# STM32_Home_Automation.net
KiCad netlist of a schematic drawn in Altium Designer
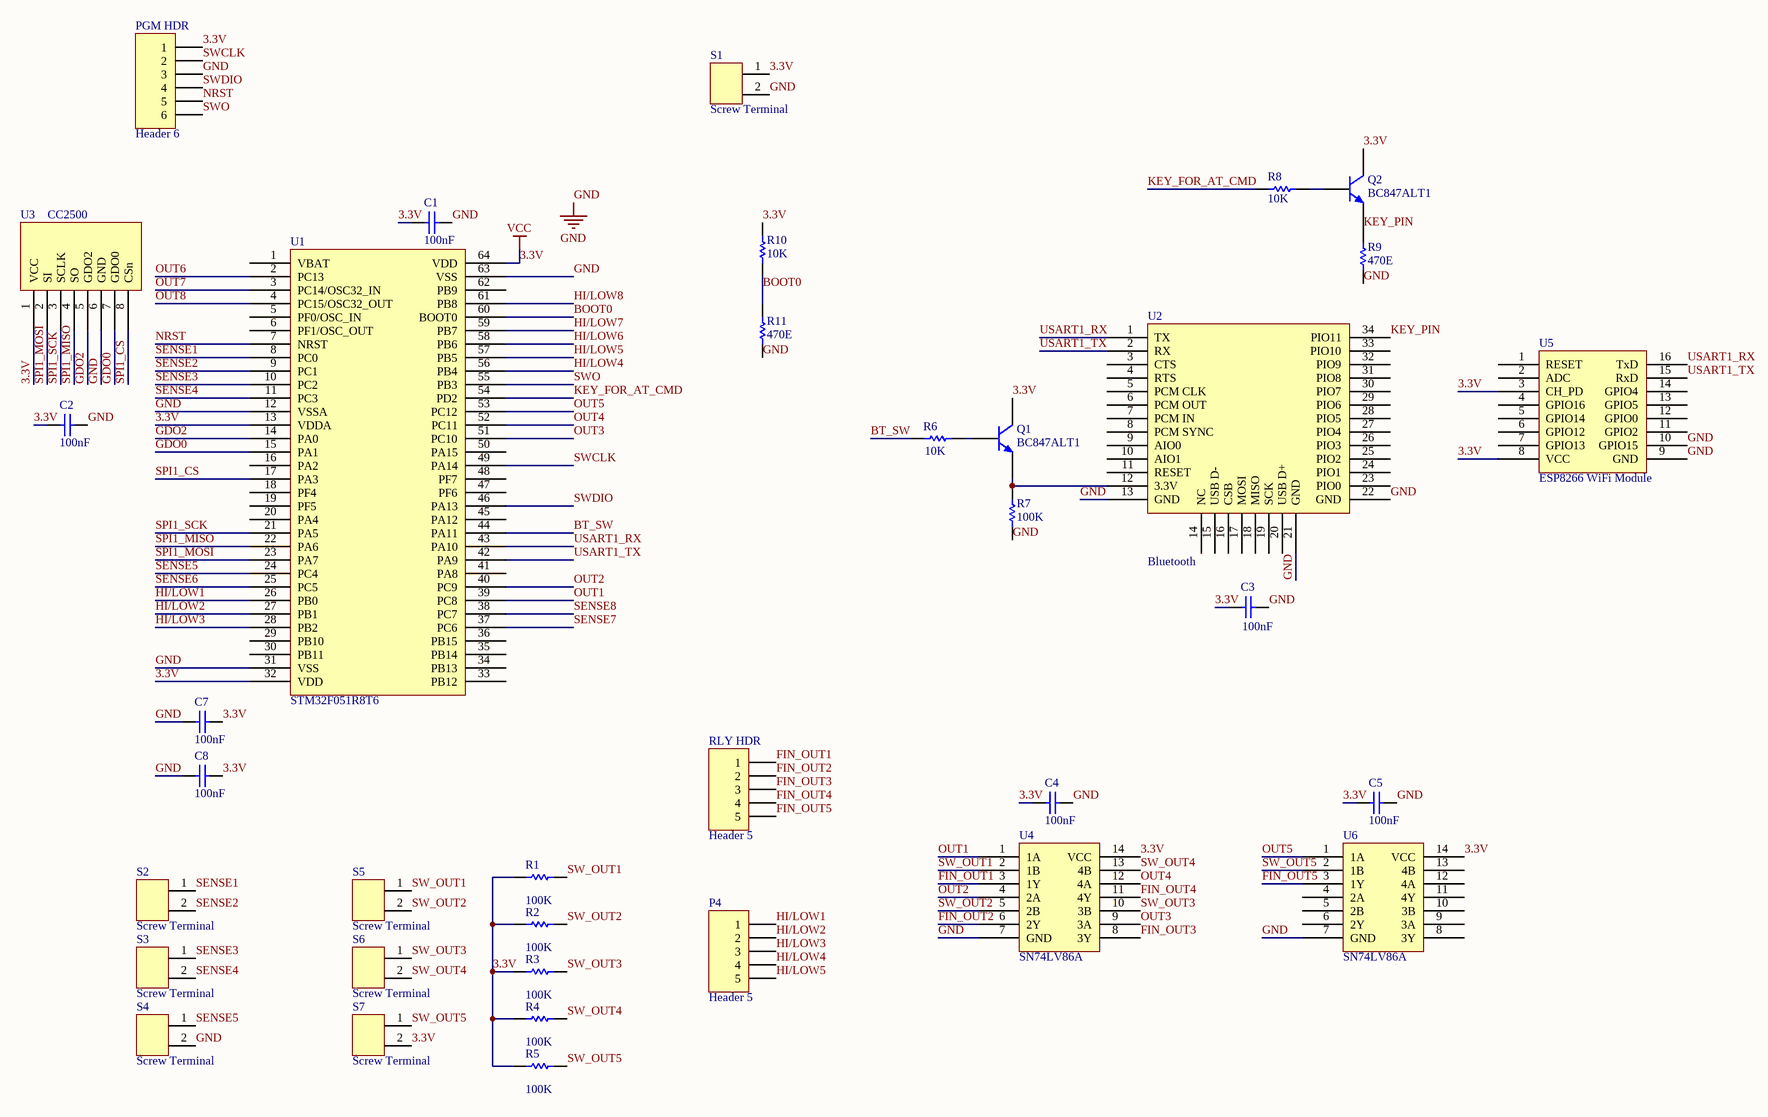
[diagram p0: STM32 Home Automation.SchDoc]

(export (version "E")
  (design (tool "Eeschema 10.0.6"))
  (components
    (comp (ref "C1")
      (value "100nF")
      (footprint "0805")
      (description "Ceramic Chip Capacitor - Standard")
      (fields (field (name "PUBLISHER") "Altium Limited"))
      (libsource (lib "KEMET Chip Capacitor") (part "C0805"))
    )
    (comp (ref "C2")
      (value "100nF")
      (footprint "0805")
      (description "Ceramic Chip Capacitor - Standard")
      (fields (field (name "PUBLISHER") "Altium Limited"))
      (libsource (lib "KEMET Chip Capacitor") (part "C0805"))
    )
    (comp (ref "C3")
      (value "100nF")
      (footprint "0805")
      (description "Ceramic Chip Capacitor - Standard")
      (fields (field (name "PUBLISHER") "Altium Limited"))
      (libsource (lib "KEMET Chip Capacitor") (part "C0805"))
    )
    (comp (ref "C4")
      (value "100nF")
      (footprint "0805")
      (description "Ceramic Chip Capacitor - Standard")
      (fields (field (name "PUBLISHER") "Altium Limited"))
      (libsource (lib "KEMET Chip Capacitor") (part "C0805"))
    )
    (comp (ref "C5")
      (value "100nF")
      (footprint "0805")
      (description "Ceramic Chip Capacitor - Standard")
      (fields (field (name "PUBLISHER") "Altium Limited"))
      (libsource (lib "KEMET Chip Capacitor") (part "C0805"))
    )
    (comp (ref "C7")
      (value "100nF")
      (footprint "0805")
      (description "Ceramic Chip Capacitor - Standard")
      (fields (field (name "PUBLISHER") "Altium Limited"))
      (libsource (lib "KEMET Chip Capacitor") (part "C0805"))
    )
    (comp (ref "C8")
      (value "100nF")
      (footprint "0805")
      (description "Ceramic Chip Capacitor - Standard")
      (fields (field (name "PUBLISHER") "Altium Limited"))
      (libsource (lib "KEMET Chip Capacitor") (part "C0805"))
    )
    (comp (ref "P4")
      (value "Header 5")
      (footprint "HDR1X5")
      (description "Header, 5-Pin")
      (fields (field (name "PUBLISHER") "Altium Limited"))
      (libsource (lib "Miscellaneous Connectors") (part "Header 5"))
    )
    (comp (ref "PGM HDR")
      (value "Header 6")
      (footprint "HDR1X6")
      (description "Header, 6-Pin")
      (fields (field (name "PUBLISHER") "Altium Limited"))
      (libsource (lib "Miscellaneous Connectors") (part "Header 6"))
    )
    (comp (ref "Q1")
      (value "BC847ALT1")
      (footprint "318-08")
      (description "General Purpose Transistor NPN Silicon")
      (fields (field (name "PUBLISHER") "Altium Limited"))
      (libsource (lib "Motorola Discrete BJT") (part "BC847ALT1"))
    )
    (comp (ref "Q2")
      (value "BC847ALT1")
      (footprint "318-08")
      (description "General Purpose Transistor NPN Silicon")
      (fields (field (name "PUBLISHER") "Altium Limited"))
      (libsource (lib "Motorola Discrete BJT") (part "BC847ALT1"))
    )
    (comp (ref "R1")
      (value "100K")
      (footprint "ERA-0805")
      (fields (field (name "PUBLISHER") "Altium Limited"))
      (libsource (lib "Panasonic Resistor") (part "ERA6Y"))
    )
    (comp (ref "R2")
      (value "100K")
      (footprint "ERA-0805")
      (fields (field (name "PUBLISHER") "Altium Limited"))
      (libsource (lib "Panasonic Resistor") (part "ERA6Y"))
    )
    (comp (ref "R3")
      (value "100K")
      (footprint "ERA-0805")
      (fields (field (name "PUBLISHER") "Altium Limited"))
      (libsource (lib "Panasonic Resistor") (part "ERA6Y"))
    )
    (comp (ref "R4")
      (value "100K")
      (footprint "ERA-0805")
      (fields (field (name "PUBLISHER") "Altium Limited"))
      (libsource (lib "Panasonic Resistor") (part "ERA6Y"))
    )
    (comp (ref "R5")
      (value "100K")
      (footprint "ERA-0805")
      (fields (field (name "PUBLISHER") "Altium Limited"))
      (libsource (lib "Panasonic Resistor") (part "ERA6Y"))
    )
    (comp (ref "R6")
      (value "10K")
      (footprint "ERA-0805")
      (fields (field (name "PUBLISHER") "Altium Limited"))
      (libsource (lib "Panasonic Resistor") (part "ERA6Y"))
    )
    (comp (ref "R7")
      (value "100K")
      (footprint "ERA-0805")
      (fields (field (name "PUBLISHER") "Altium Limited"))
      (libsource (lib "Panasonic Resistor") (part "ERA6Y"))
    )
    (comp (ref "R8")
      (value "10K")
      (footprint "ERA-0805")
      (fields (field (name "PUBLISHER") "Altium Limited"))
      (libsource (lib "Panasonic Resistor") (part "ERA6Y"))
    )
    (comp (ref "R9")
      (value "470E")
      (footprint "ERA-0805")
      (fields (field (name "PUBLISHER") "Altium Limited"))
      (libsource (lib "Panasonic Resistor") (part "ERA6Y"))
    )
    (comp (ref "R10")
      (value "10K")
      (footprint "ERA-0805")
      (fields (field (name "PUBLISHER") "Altium Limited"))
      (libsource (lib "Panasonic Resistor") (part "ERA6Y"))
    )
    (comp (ref "R11")
      (value "470E")
      (footprint "ERA-0805")
      (fields (field (name "PUBLISHER") "Altium Limited"))
      (libsource (lib "Panasonic Resistor") (part "ERA6Y"))
    )
    (comp (ref "RLY HDR")
      (value "Header 5")
      (footprint "HDR1X5")
      (description "Header, 5-Pin")
      (fields (field (name "PUBLISHER") "Altium Limited"))
      (libsource (lib "Miscellaneous Connectors") (part "Header 5"))
    )
    (comp (ref "S1")
      (value "Screw Terminal")
      (footprint "Screw Terminal")
      (libsource (lib "2 Pin") (part "Screw Terminal"))
    )
    (comp (ref "S2")
      (value "Screw Terminal")
      (footprint "Screw Terminal")
      (libsource (lib "2 Pin") (part "Screw Terminal"))
    )
    (comp (ref "S3")
      (value "Screw Terminal")
      (footprint "Screw Terminal")
      (libsource (lib "2 Pin") (part "Screw Terminal"))
    )
    (comp (ref "S4")
      (value "Screw Terminal")
      (footprint "Screw Terminal")
      (libsource (lib "2 Pin") (part "Screw Terminal"))
    )
    (comp (ref "S5")
      (value "Screw Terminal")
      (footprint "Screw Terminal")
      (libsource (lib "2 Pin") (part "Screw Terminal"))
    )
    (comp (ref "S6")
      (value "Screw Terminal")
      (footprint "Screw Terminal")
      (libsource (lib "2 Pin") (part "Screw Terminal"))
    )
    (comp (ref "S7")
      (value "Screw Terminal")
      (footprint "Screw Terminal")
      (libsource (lib "2 Pin") (part "Screw Terminal"))
    )
    (comp (ref "U1")
      (value "STM32F051R8T6")
      (footprint "STM32F051R8T6")
      (libsource (lib "STM32F051R8T6") (part "STM32F051R8T6"))
    )
    (comp (ref "U2")
      (value "Bluetooth")
      (footprint "Bluetooth")
      (libsource (lib "Bluetooth") (part "Bluetooth"))
    )
    (comp (ref "U3") (value "CC2500") (footprint "CC2500") (libsource (lib "CC2500") (part "CC2500")))
    (comp (ref "U4")
      (value "SN74LV86A")
      (footprint "SN74LV86A, SOIC127P600X175-14N")
      (libsource (lib "SN74LV86A.") (part "SN74LV86A"))
    )
    (comp (ref "U5") (value "ESP8266 WiFi Module") (libsource (lib "ESP8266") (part "ESP8266 WiFi Module")))
    (comp (ref "U6")
      (value "SN74LV86A")
      (footprint "SN74LV86A, SOIC127P600X175-14N")
      (libsource (lib "SN74LV86A.") (part "SN74LV86A"))
    )
  )
  (nets
    (net (code "1") (name "/BOOT0") (class "Default")
      (node (ref "R10") (pin "2") (pinfunction "2_2") (pintype "passive"))
      (node (ref "R11") (pin "1") (pinfunction "1_1") (pintype "passive"))
      (node (ref "U1") (pin "60") (pinfunction "BOOT0_60") (pintype "passive"))
    )
    (net (code "2") (name "/BT_SW") (class "Default")
      (node (ref "R6") (pin "1") (pinfunction "1_1") (pintype "passive"))
      (node (ref "U1") (pin "44") (pinfunction "PA11_44") (pintype "passive"))
    )
    (net (code "3") (name "/FIN_OUT1") (class "Default")
      (node (ref "RLY HDR") (pin "1") (pinfunction "1_1") (pintype "passive"))
      (node (ref "U4") (pin "3") (pinfunction "1Y_3") (pintype "passive"))
    )
    (net (code "4") (name "/FIN_OUT2") (class "Default")
      (node (ref "RLY HDR") (pin "2") (pinfunction "2_2") (pintype "passive"))
      (node (ref "U4") (pin "6") (pinfunction "2Y_6") (pintype "passive"))
    )
    (net (code "5") (name "/FIN_OUT3") (class "Default")
      (node (ref "RLY HDR") (pin "3") (pinfunction "3_3") (pintype "passive"))
      (node (ref "U4") (pin "8") (pinfunction "3Y_8") (pintype "passive"))
    )
    (net (code "6") (name "/FIN_OUT4") (class "Default")
      (node (ref "RLY HDR") (pin "4") (pinfunction "4_4") (pintype "passive"))
      (node (ref "U4") (pin "11") (pinfunction "4Y_11") (pintype "passive"))
    )
    (net (code "7") (name "/FIN_OUT5") (class "Default")
      (node (ref "RLY HDR") (pin "5") (pinfunction "5_5") (pintype "passive"))
      (node (ref "U6") (pin "3") (pinfunction "1Y_3") (pintype "passive"))
    )
    (net (code "8") (name "/GDO0") (class "Default")
      (node (ref "U1") (pin "15") (pinfunction "PA1_15") (pintype "passive"))
      (node (ref "U3") (pin "7") (pinfunction "GDO0_7") (pintype "passive"))
    )
    (net (code "9") (name "/GDO2") (class "Default")
      (node (ref "U1") (pin "14") (pinfunction "PA0_14") (pintype "passive"))
      (node (ref "U3") (pin "5") (pinfunction "GDO2_5") (pintype "passive"))
    )
    (net (code "10") (name "/HI{slash}LOW1") (class "Default")
      (node (ref "P4") (pin "1") (pinfunction "1_1") (pintype "passive"))
      (node (ref "U1") (pin "26") (pinfunction "PB0_26") (pintype "passive"))
    )
    (net (code "11") (name "/HI{slash}LOW2") (class "Default")
      (node (ref "P4") (pin "2") (pinfunction "2_2") (pintype "passive"))
      (node (ref "U1") (pin "27") (pinfunction "PB1_27") (pintype "passive"))
    )
    (net (code "12") (name "/HI{slash}LOW3") (class "Default")
      (node (ref "P4") (pin "3") (pinfunction "3_3") (pintype "passive"))
      (node (ref "U1") (pin "28") (pinfunction "PB2_28") (pintype "passive"))
    )
    (net (code "13") (name "/HI{slash}LOW4") (class "Default")
      (node (ref "P4") (pin "4") (pinfunction "4_4") (pintype "passive"))
      (node (ref "U1") (pin "56") (pinfunction "PB4_56") (pintype "passive"))
    )
    (net (code "14") (name "/HI{slash}LOW5") (class "Default")
      (node (ref "P4") (pin "5") (pinfunction "5_5") (pintype "passive"))
      (node (ref "U1") (pin "57") (pinfunction "PB5_57") (pintype "passive"))
    )
    (net (code "15") (name "/HI{slash}LOW6") (class "Default")
      (node (ref "U1") (pin "58") (pinfunction "PB6_58") (pintype "passive"))
    )
    (net (code "16") (name "/HI{slash}LOW7") (class "Default")
      (node (ref "U1") (pin "59") (pinfunction "PB7_59") (pintype "passive"))
    )
    (net (code "17") (name "/HI{slash}LOW8") (class "Default")
      (node (ref "U1") (pin "61") (pinfunction "PB8_61") (pintype "passive"))
    )
    (net (code "18") (name "/KEY_FOR_AT_CMD") (class "Default")
      (node (ref "R8") (pin "2") (pinfunction "2_2") (pintype "passive"))
      (node (ref "U1") (pin "54") (pinfunction "PD2_54") (pintype "passive"))
    )
    (net (code "19") (name "/KEY_PIN") (class "Default")
      (node (ref "Q2") (pin "2") (pinfunction "E_2") (pintype "passive"))
      (node (ref "R9") (pin "1") (pinfunction "1_1") (pintype "passive"))
      (node (ref "U2") (pin "34") (pinfunction "PIO11_34") (pintype "passive"))
    )
    (net (code "20") (name "/NRST") (class "Default")
      (node (ref "PGM HDR") (pin "5") (pinfunction "5_5") (pintype "passive"))
      (node (ref "U1") (pin "7") (pinfunction "NRST_7") (pintype "passive"))
    )
    (net (code "21") (name "/OUT1") (class "Default")
      (node (ref "U1") (pin "39") (pinfunction "PC8_39") (pintype "passive"))
      (node (ref "U4") (pin "1") (pinfunction "1A_1") (pintype "passive"))
    )
    (net (code "22") (name "/OUT2") (class "Default")
      (node (ref "U1") (pin "40") (pinfunction "PC9_40") (pintype "passive"))
      (node (ref "U4") (pin "4") (pinfunction "2A_4") (pintype "passive"))
    )
    (net (code "23") (name "/OUT3") (class "Default")
      (node (ref "U1") (pin "51") (pinfunction "PC10_51") (pintype "passive"))
      (node (ref "U4") (pin "9") (pinfunction "3A_9") (pintype "passive"))
    )
    (net (code "24") (name "/OUT4") (class "Default")
      (node (ref "U1") (pin "52") (pinfunction "PC11_52") (pintype "passive"))
      (node (ref "U4") (pin "12") (pinfunction "4A_12") (pintype "passive"))
    )
    (net (code "25") (name "/OUT5") (class "Default")
      (node (ref "U1") (pin "53") (pinfunction "PC12_53") (pintype "passive"))
      (node (ref "U6") (pin "1") (pinfunction "1A_1") (pintype "passive"))
    )
    (net (code "26") (name "/OUT6") (class "Default")
      (node (ref "U1") (pin "2") (pinfunction "PC13_2") (pintype "passive"))
    )
    (net (code "27") (name "/OUT7") (class "Default")
      (node (ref "U1") (pin "3") (pinfunction "PC14/OSC32_IN_3") (pintype "passive"))
    )
    (net (code "28") (name "/OUT8") (class "Default")
      (node (ref "U1") (pin "4") (pinfunction "PC15/OSC32_OUT_4") (pintype "passive"))
    )
    (net (code "29") (name "/SENSE1") (class "Default")
      (node (ref "S2") (pin "1") (pintype "passive"))
      (node (ref "U1") (pin "8") (pinfunction "PC0_8") (pintype "passive"))
    )
    (net (code "30") (name "/SENSE2") (class "Default")
      (node (ref "S2") (pin "2") (pintype "passive"))
      (node (ref "U1") (pin "9") (pinfunction "PC1_9") (pintype "passive"))
    )
    (net (code "31") (name "/SENSE3") (class "Default")
      (node (ref "S3") (pin "1") (pintype "passive"))
      (node (ref "U1") (pin "10") (pinfunction "PC2_10") (pintype "passive"))
    )
    (net (code "32") (name "/SENSE4") (class "Default")
      (node (ref "S3") (pin "2") (pintype "passive"))
      (node (ref "U1") (pin "11") (pinfunction "PC3_11") (pintype "passive"))
    )
    (net (code "33") (name "/SENSE5") (class "Default")
      (node (ref "S4") (pin "1") (pintype "passive"))
      (node (ref "U1") (pin "24") (pinfunction "PC4_24") (pintype "passive"))
    )
    (net (code "34") (name "/SENSE6") (class "Default")
      (node (ref "U1") (pin "25") (pinfunction "PC5_25") (pintype "passive"))
    )
    (net (code "35") (name "/SENSE7") (class "Default")
      (node (ref "U1") (pin "37") (pinfunction "PC6_37") (pintype "passive"))
    )
    (net (code "36") (name "/SENSE8") (class "Default")
      (node (ref "U1") (pin "38") (pinfunction "PC7_38") (pintype "passive"))
    )
    (net (code "37") (name "/SPI1_CS") (class "Default")
      (node (ref "U1") (pin "17") (pinfunction "PA3_17") (pintype "passive"))
      (node (ref "U3") (pin "8") (pinfunction "CSn_8") (pintype "passive"))
    )
    (net (code "38") (name "/SPI1_MISO") (class "Default")
      (node (ref "U1") (pin "22") (pinfunction "PA6_22") (pintype "passive"))
      (node (ref "U3") (pin "4") (pinfunction "SO_4") (pintype "passive"))
    )
    (net (code "39") (name "/SPI1_MOSI") (class "Default")
      (node (ref "U1") (pin "23") (pinfunction "PA7_23") (pintype "passive"))
      (node (ref "U3") (pin "2") (pinfunction "SI_2") (pintype "passive"))
    )
    (net (code "40") (name "/SPI1_SCK") (class "Default")
      (node (ref "U1") (pin "21") (pinfunction "PA5_21") (pintype "passive"))
      (node (ref "U3") (pin "3") (pinfunction "SCLK_3") (pintype "passive"))
    )
    (net (code "41") (name "/SWCLK") (class "Default")
      (node (ref "PGM HDR") (pin "2") (pinfunction "2_2") (pintype "passive"))
      (node (ref "U1") (pin "49") (pinfunction "PA14_49") (pintype "passive"))
    )
    (net (code "42") (name "/SWDIO") (class "Default")
      (node (ref "PGM HDR") (pin "4") (pinfunction "4_4") (pintype "passive"))
      (node (ref "U1") (pin "46") (pinfunction "PA13_46") (pintype "passive"))
    )
    (net (code "43") (name "/SWO") (class "Default")
      (node (ref "PGM HDR") (pin "6") (pinfunction "6_6") (pintype "passive"))
      (node (ref "U1") (pin "55") (pinfunction "PB3_55") (pintype "passive"))
    )
    (net (code "44") (name "/SW_OUT1") (class "Default")
      (node (ref "R1") (pin "2") (pinfunction "2_2") (pintype "passive"))
      (node (ref "S5") (pin "1") (pintype "passive"))
      (node (ref "U4") (pin "2") (pinfunction "1B_2") (pintype "passive"))
    )
    (net (code "45") (name "/SW_OUT2") (class "Default")
      (node (ref "R2") (pin "2") (pinfunction "2_2") (pintype "passive"))
      (node (ref "S5") (pin "2") (pintype "passive"))
      (node (ref "U4") (pin "5") (pinfunction "2B_5") (pintype "passive"))
    )
    (net (code "46") (name "/SW_OUT3") (class "Default")
      (node (ref "R3") (pin "2") (pinfunction "2_2") (pintype "passive"))
      (node (ref "S6") (pin "1") (pintype "passive"))
      (node (ref "U4") (pin "10") (pinfunction "3B_10") (pintype "passive"))
    )
    (net (code "47") (name "/SW_OUT4") (class "Default")
      (node (ref "R4") (pin "2") (pinfunction "2_2") (pintype "passive"))
      (node (ref "S6") (pin "2") (pintype "passive"))
      (node (ref "U4") (pin "13") (pinfunction "4B_13") (pintype "passive"))
    )
    (net (code "48") (name "/SW_OUT5") (class "Default")
      (node (ref "R5") (pin "2") (pinfunction "2_2") (pintype "passive"))
      (node (ref "S7") (pin "1") (pintype "passive"))
      (node (ref "U6") (pin "2") (pinfunction "1B_2") (pintype "passive"))
    )
    (net (code "49") (name "/USART1_RX") (class "Default")
      (node (ref "U1") (pin "43") (pinfunction "PA10_43") (pintype "passive"))
      (node (ref "U2") (pin "1") (pinfunction "TX_1") (pintype "passive"))
      (node (ref "U5") (pin "16") (pinfunction "TxD_16") (pintype "passive"))
    )
    (net (code "50") (name "/USART1_TX") (class "Default")
      (node (ref "U1") (pin "42") (pinfunction "PA9_42") (pintype "passive"))
      (node (ref "U2") (pin "2") (pinfunction "RX_2") (pintype "passive"))
      (node (ref "U5") (pin "15") (pinfunction "RxD_15") (pintype "passive"))
    )
    (net (code "51") (name "GND") (class "Default")
      (node (ref "C1") (pin "2") (pinfunction "2_2") (pintype "passive"))
      (node (ref "C2") (pin "2") (pinfunction "2_2") (pintype "passive"))
      (node (ref "C3") (pin "2") (pinfunction "2_2") (pintype "passive"))
      (node (ref "C4") (pin "2") (pinfunction "2_2") (pintype "passive"))
      (node (ref "C5") (pin "2") (pinfunction "2_2") (pintype "passive"))
      (node (ref "C7") (pin "2") (pinfunction "2_2") (pintype "passive"))
      (node (ref "C8") (pin "2") (pinfunction "2_2") (pintype "passive"))
      (node (ref "PGM HDR") (pin "3") (pinfunction "3_3") (pintype "passive"))
      (node (ref "R11") (pin "2") (pinfunction "2_2") (pintype "passive"))
      (node (ref "R7") (pin "1") (pinfunction "1_1") (pintype "passive"))
      (node (ref "R9") (pin "2") (pinfunction "2_2") (pintype "passive"))
      (node (ref "S1") (pin "2") (pintype "passive"))
      (node (ref "S4") (pin "2") (pintype "passive"))
      (node (ref "U1") (pin "12") (pinfunction "VSSA_12") (pintype "passive"))
      (node (ref "U1") (pin "31") (pinfunction "VSS_31") (pintype "passive"))
      (node (ref "U1") (pin "63") (pinfunction "VSS_63") (pintype "passive"))
      (node (ref "U2") (pin "13") (pinfunction "GND_13") (pintype "passive"))
      (node (ref "U2") (pin "21") (pinfunction "GND_21") (pintype "passive"))
      (node (ref "U2") (pin "22") (pinfunction "GND_22") (pintype "passive"))
      (node (ref "U3") (pin "6") (pinfunction "GND_6") (pintype "passive"))
      (node (ref "U4") (pin "7") (pinfunction "GND_7") (pintype "passive"))
      (node (ref "U5") (pin "10") (pinfunction "GPIO15_10") (pintype "passive"))
      (node (ref "U5") (pin "9") (pinfunction "GND_9") (pintype "passive"))
      (node (ref "U6") (pin "7") (pinfunction "GND_7") (pintype "passive"))
    )
    (net (code "52") (name "Net-(Q1-B)") (class "Default")
      (node (ref "Q1") (pin "1") (pinfunction "B_1") (pintype "passive"))
      (node (ref "R6") (pin "2") (pinfunction "2_2") (pintype "passive"))
    )
    (net (code "53") (name "Net-(Q1-E)") (class "Default")
      (node (ref "Q1") (pin "2") (pinfunction "E_2") (pintype "passive"))
      (node (ref "R7") (pin "2") (pinfunction "2_2") (pintype "passive"))
      (node (ref "U2") (pin "12") (pinfunction "3.3V_12") (pintype "passive"))
    )
    (net (code "54") (name "Net-(Q2-B)") (class "Default")
      (node (ref "Q2") (pin "1") (pinfunction "B_1") (pintype "passive"))
      (node (ref "R8") (pin "1") (pinfunction "1_1") (pintype "passive"))
    )
    (net (code "55") (name "VCC") (class "Default")
      (node (ref "C1") (pin "1") (pinfunction "1_1") (pintype "passive"))
      (node (ref "C2") (pin "1") (pinfunction "1_1") (pintype "passive"))
      (node (ref "C3") (pin "1") (pinfunction "1_1") (pintype "passive"))
      (node (ref "C4") (pin "1") (pinfunction "1_1") (pintype "passive"))
      (node (ref "C5") (pin "1") (pinfunction "1_1") (pintype "passive"))
      (node (ref "C7") (pin "1") (pinfunction "1_1") (pintype "passive"))
      (node (ref "C8") (pin "1") (pinfunction "1_1") (pintype "passive"))
      (node (ref "PGM HDR") (pin "1") (pinfunction "1_1") (pintype "passive"))
      (node (ref "Q1") (pin "3") (pinfunction "C_3") (pintype "passive"))
      (node (ref "Q2") (pin "3") (pinfunction "C_3") (pintype "passive"))
      (node (ref "R1") (pin "1") (pinfunction "1_1") (pintype "passive"))
      (node (ref "R10") (pin "1") (pinfunction "1_1") (pintype "passive"))
      (node (ref "R2") (pin "1") (pinfunction "1_1") (pintype "passive"))
      (node (ref "R3") (pin "1") (pinfunction "1_1") (pintype "passive"))
      (node (ref "R4") (pin "1") (pinfunction "1_1") (pintype "passive"))
      (node (ref "R5") (pin "1") (pinfunction "1_1") (pintype "passive"))
      (node (ref "S1") (pin "1") (pintype "passive"))
      (node (ref "S7") (pin "2") (pintype "passive"))
      (node (ref "U1") (pin "13") (pinfunction "VDDA_13") (pintype "passive"))
      (node (ref "U1") (pin "32") (pinfunction "VDD_32") (pintype "passive"))
      (node (ref "U1") (pin "64") (pinfunction "VDD_64") (pintype "passive"))
      (node (ref "U3") (pin "1") (pinfunction "VCC_1") (pintype "passive"))
      (node (ref "U4") (pin "14") (pinfunction "VCC_14") (pintype "passive"))
      (node (ref "U5") (pin "3") (pinfunction "CH_PD_3") (pintype "passive"))
      (node (ref "U5") (pin "8") (pinfunction "VCC_8") (pintype "passive"))
      (node (ref "U6") (pin "14") (pinfunction "VCC_14") (pintype "passive"))
    )
    (net (code "56") (name "unconnected-(U1-PA2-Pad16)") (class "Default")
      (node (ref "U1") (pin "16") (pinfunction "PA2_16") (pintype "passive"))
    )
    (net (code "57") (name "unconnected-(U1-PA4-Pad20)") (class "Default")
      (node (ref "U1") (pin "20") (pinfunction "PA4_20") (pintype "passive"))
    )
    (net (code "58") (name "unconnected-(U1-PA8-Pad41)") (class "Default")
      (node (ref "U1") (pin "41") (pinfunction "PA8_41") (pintype "passive"))
    )
    (net (code "59") (name "unconnected-(U1-PA12-Pad45)") (class "Default")
      (node (ref "U1") (pin "45") (pinfunction "PA12_45") (pintype "passive"))
    )
    (net (code "60") (name "unconnected-(U1-PA15-Pad50)") (class "Default")
      (node (ref "U1") (pin "50") (pinfunction "PA15_50") (pintype "passive"))
    )
    (net (code "61") (name "unconnected-(U1-PB9-Pad62)") (class "Default")
      (node (ref "U1") (pin "62") (pinfunction "PB9_62") (pintype "passive"))
    )
    (net (code "62") (name "unconnected-(U1-PB10-Pad29)") (class "Default")
      (node (ref "U1") (pin "29") (pinfunction "PB10_29") (pintype "passive"))
    )
    (net (code "63") (name "unconnected-(U1-PB11-Pad30)") (class "Default")
      (node (ref "U1") (pin "30") (pinfunction "PB11_30") (pintype "passive"))
    )
    (net (code "64") (name "unconnected-(U1-PB12-Pad33)") (class "Default")
      (node (ref "U1") (pin "33") (pinfunction "PB12_33") (pintype "passive"))
    )
    (net (code "65") (name "unconnected-(U1-PB13-Pad34)") (class "Default")
      (node (ref "U1") (pin "34") (pinfunction "PB13_34") (pintype "passive"))
    )
    (net (code "66") (name "unconnected-(U1-PB14-Pad35)") (class "Default")
      (node (ref "U1") (pin "35") (pinfunction "PB14_35") (pintype "passive"))
    )
    (net (code "67") (name "unconnected-(U1-PB15-Pad36)") (class "Default")
      (node (ref "U1") (pin "36") (pinfunction "PB15_36") (pintype "passive"))
    )
    (net (code "68") (name "unconnected-(U1-PF0{slash}OSC_IN-Pad5)") (class "Default")
      (node (ref "U1") (pin "5") (pinfunction "PF0/OSC_IN_5") (pintype "passive"))
    )
    (net (code "69") (name "unconnected-(U1-PF1{slash}OSC_OUT-Pad6)") (class "Default")
      (node (ref "U1") (pin "6") (pinfunction "PF1/OSC_OUT_6") (pintype "passive"))
    )
    (net (code "70") (name "unconnected-(U1-PF4-Pad18)") (class "Default")
      (node (ref "U1") (pin "18") (pinfunction "PF4_18") (pintype "passive"))
    )
    (net (code "71") (name "unconnected-(U1-PF5-Pad19)") (class "Default")
      (node (ref "U1") (pin "19") (pinfunction "PF5_19") (pintype "passive"))
    )
    (net (code "72") (name "unconnected-(U1-PF6-Pad47)") (class "Default")
      (node (ref "U1") (pin "47") (pinfunction "PF6_47") (pintype "passive"))
    )
    (net (code "73") (name "unconnected-(U1-PF7-Pad48)") (class "Default")
      (node (ref "U1") (pin "48") (pinfunction "PF7_48") (pintype "passive"))
    )
    (net (code "74") (name "unconnected-(U1-VBAT-Pad1)") (class "Default")
      (node (ref "U1") (pin "1") (pinfunction "VBAT_1") (pintype "passive"))
    )
    (net (code "75") (name "unconnected-(U2-AIO0-Pad9)") (class "Default")
      (node (ref "U2") (pin "9") (pinfunction "AIO0_9") (pintype "passive"))
    )
    (net (code "76") (name "unconnected-(U2-AIO1-Pad10)") (class "Default")
      (node (ref "U2") (pin "10") (pinfunction "AIO1_10") (pintype "passive"))
    )
    (net (code "77") (name "unconnected-(U2-CSB-Pad16)") (class "Default")
      (node (ref "U2") (pin "16") (pinfunction "CSB_16") (pintype "passive"))
    )
    (net (code "78") (name "unconnected-(U2-CTS-Pad3)") (class "Default")
      (node (ref "U2") (pin "3") (pinfunction "CTS_3") (pintype "passive"))
    )
    (net (code "79") (name "unconnected-(U2-MISO-Pad18)") (class "Default")
      (node (ref "U2") (pin "18") (pinfunction "MISO_18") (pintype "passive"))
    )
    (net (code "80") (name "unconnected-(U2-MOSI-Pad17)") (class "Default")
      (node (ref "U2") (pin "17") (pinfunction "MOSI_17") (pintype "passive"))
    )
    (net (code "81") (name "unconnected-(U2-NC-Pad14)") (class "Default")
      (node (ref "U2") (pin "14") (pinfunction "NC_14") (pintype "passive"))
    )
    (net (code "82") (name "unconnected-(U2-PCM_CLK-Pad5)") (class "Default")
      (node (ref "U2") (pin "5") (pinfunction "PCM_CLK_5") (pintype "passive"))
    )
    (net (code "83") (name "unconnected-(U2-PCM_IN-Pad7)") (class "Default")
      (node (ref "U2") (pin "7") (pinfunction "PCM_IN_7") (pintype "passive"))
    )
    (net (code "84") (name "unconnected-(U2-PCM_OUT-Pad6)") (class "Default")
      (node (ref "U2") (pin "6") (pinfunction "PCM_OUT_6") (pintype "passive"))
    )
    (net (code "85") (name "unconnected-(U2-PCM_SYNC-Pad8)") (class "Default")
      (node (ref "U2") (pin "8") (pinfunction "PCM_SYNC_8") (pintype "passive"))
    )
    (net (code "86") (name "unconnected-(U2-PIO0-Pad23)") (class "Default")
      (node (ref "U2") (pin "23") (pinfunction "PIO0_23") (pintype "passive"))
    )
    (net (code "87") (name "unconnected-(U2-PIO1-Pad24)") (class "Default")
      (node (ref "U2") (pin "24") (pinfunction "PIO1_24") (pintype "passive"))
    )
    (net (code "88") (name "unconnected-(U2-PIO2-Pad25)") (class "Default")
      (node (ref "U2") (pin "25") (pinfunction "PIO2_25") (pintype "passive"))
    )
    (net (code "89") (name "unconnected-(U2-PIO3-Pad26)") (class "Default")
      (node (ref "U2") (pin "26") (pinfunction "PIO3_26") (pintype "passive"))
    )
    (net (code "90") (name "unconnected-(U2-PIO4-Pad27)") (class "Default")
      (node (ref "U2") (pin "27") (pinfunction "PIO4_27") (pintype "passive"))
    )
    (net (code "91") (name "unconnected-(U2-PIO5-Pad28)") (class "Default")
      (node (ref "U2") (pin "28") (pinfunction "PIO5_28") (pintype "passive"))
    )
    (net (code "92") (name "unconnected-(U2-PIO6-Pad29)") (class "Default")
      (node (ref "U2") (pin "29") (pinfunction "PIO6_29") (pintype "passive"))
    )
    (net (code "93") (name "unconnected-(U2-PIO7-Pad30)") (class "Default")
      (node (ref "U2") (pin "30") (pinfunction "PIO7_30") (pintype "passive"))
    )
    (net (code "94") (name "unconnected-(U2-PIO8-Pad31)") (class "Default")
      (node (ref "U2") (pin "31") (pinfunction "PIO8_31") (pintype "passive"))
    )
    (net (code "95") (name "unconnected-(U2-PIO9-Pad32)") (class "Default")
      (node (ref "U2") (pin "32") (pinfunction "PIO9_32") (pintype "passive"))
    )
    (net (code "96") (name "unconnected-(U2-PIO10-Pad33)") (class "Default")
      (node (ref "U2") (pin "33") (pinfunction "PIO10_33") (pintype "passive"))
    )
    (net (code "97") (name "unconnected-(U2-RESET-Pad11)") (class "Default")
      (node (ref "U2") (pin "11") (pinfunction "RESET_11") (pintype "passive"))
    )
    (net (code "98") (name "unconnected-(U2-RTS-Pad4)") (class "Default")
      (node (ref "U2") (pin "4") (pinfunction "RTS_4") (pintype "passive"))
    )
    (net (code "99") (name "unconnected-(U2-SCK-Pad19)") (class "Default")
      (node (ref "U2") (pin "19") (pinfunction "SCK_19") (pintype "passive"))
    )
    (net (code "100") (name "unconnected-(U2-USB_D+-Pad20)") (class "Default")
      (node (ref "U2") (pin "20") (pinfunction "USB_D+_20") (pintype "passive"))
    )
    (net (code "101") (name "unconnected-(U2-USB_D--Pad15)") (class "Default")
      (node (ref "U2") (pin "15") (pinfunction "USB_D-_15") (pintype "passive"))
    )
    (net (code "102") (name "unconnected-(U5-ADC-Pad2)") (class "Default")
      (node (ref "U5") (pin "2") (pinfunction "ADC_2") (pintype "passive"))
    )
    (net (code "103") (name "unconnected-(U5-GPIO0-Pad12)") (class "Default")
      (node (ref "U5") (pin "12") (pinfunction "GPIO0_12") (pintype "passive"))
    )
    (net (code "104") (name "unconnected-(U5-GPIO2-Pad11)") (class "Default")
      (node (ref "U5") (pin "11") (pinfunction "GPIO2_11") (pintype "passive"))
    )
    (net (code "105") (name "unconnected-(U5-GPIO4-Pad14)") (class "Default")
      (node (ref "U5") (pin "14") (pinfunction "GPIO4_14") (pintype "passive"))
    )
    (net (code "106") (name "unconnected-(U5-GPIO5-Pad13)") (class "Default")
      (node (ref "U5") (pin "13") (pinfunction "GPIO5_13") (pintype "passive"))
    )
    (net (code "107") (name "unconnected-(U5-GPIO12-Pad6)") (class "Default")
      (node (ref "U5") (pin "6") (pinfunction "GPIO12_6") (pintype "passive"))
    )
    (net (code "108") (name "unconnected-(U5-GPIO13-Pad7)") (class "Default")
      (node (ref "U5") (pin "7") (pinfunction "GPIO13_7") (pintype "passive"))
    )
    (net (code "109") (name "unconnected-(U5-GPIO14-Pad5)") (class "Default")
      (node (ref "U5") (pin "5") (pinfunction "GPIO14_5") (pintype "passive"))
    )
    (net (code "110") (name "unconnected-(U5-GPIO16-Pad4)") (class "Default")
      (node (ref "U5") (pin "4") (pinfunction "GPIO16_4") (pintype "passive"))
    )
    (net (code "111") (name "unconnected-(U5-RESET-Pad1)") (class "Default")
      (node (ref "U5") (pin "1") (pinfunction "RESET_1") (pintype "passive"))
    )
    (net (code "112") (name "unconnected-(U6-2A-Pad4)") (class "Default")
      (node (ref "U6") (pin "4") (pinfunction "2A_4") (pintype "passive"))
    )
    (net (code "113") (name "unconnected-(U6-2B-Pad5)") (class "Default")
      (node (ref "U6") (pin "5") (pinfunction "2B_5") (pintype "passive"))
    )
    (net (code "114") (name "unconnected-(U6-2Y-Pad6)") (class "Default")
      (node (ref "U6") (pin "6") (pinfunction "2Y_6") (pintype "passive"))
    )
    (net (code "115") (name "unconnected-(U6-3A-Pad9)") (class "Default")
      (node (ref "U6") (pin "9") (pinfunction "3A_9") (pintype "passive"))
    )
    (net (code "116") (name "unconnected-(U6-3B-Pad10)") (class "Default")
      (node (ref "U6") (pin "10") (pinfunction "3B_10") (pintype "passive"))
    )
    (net (code "117") (name "unconnected-(U6-3Y-Pad8)") (class "Default")
      (node (ref "U6") (pin "8") (pinfunction "3Y_8") (pintype "passive"))
    )
    (net (code "118") (name "unconnected-(U6-4A-Pad12)") (class "Default")
      (node (ref "U6") (pin "12") (pinfunction "4A_12") (pintype "passive"))
    )
    (net (code "119") (name "unconnected-(U6-4B-Pad13)") (class "Default")
      (node (ref "U6") (pin "13") (pinfunction "4B_13") (pintype "passive"))
    )
    (net (code "120") (name "unconnected-(U6-4Y-Pad11)") (class "Default")
      (node (ref "U6") (pin "11") (pinfunction "4Y_11") (pintype "passive"))
    )
  )
)
